# UART_2_MUX.net
KiCad netlist of a schematic drawn in Altium Designer
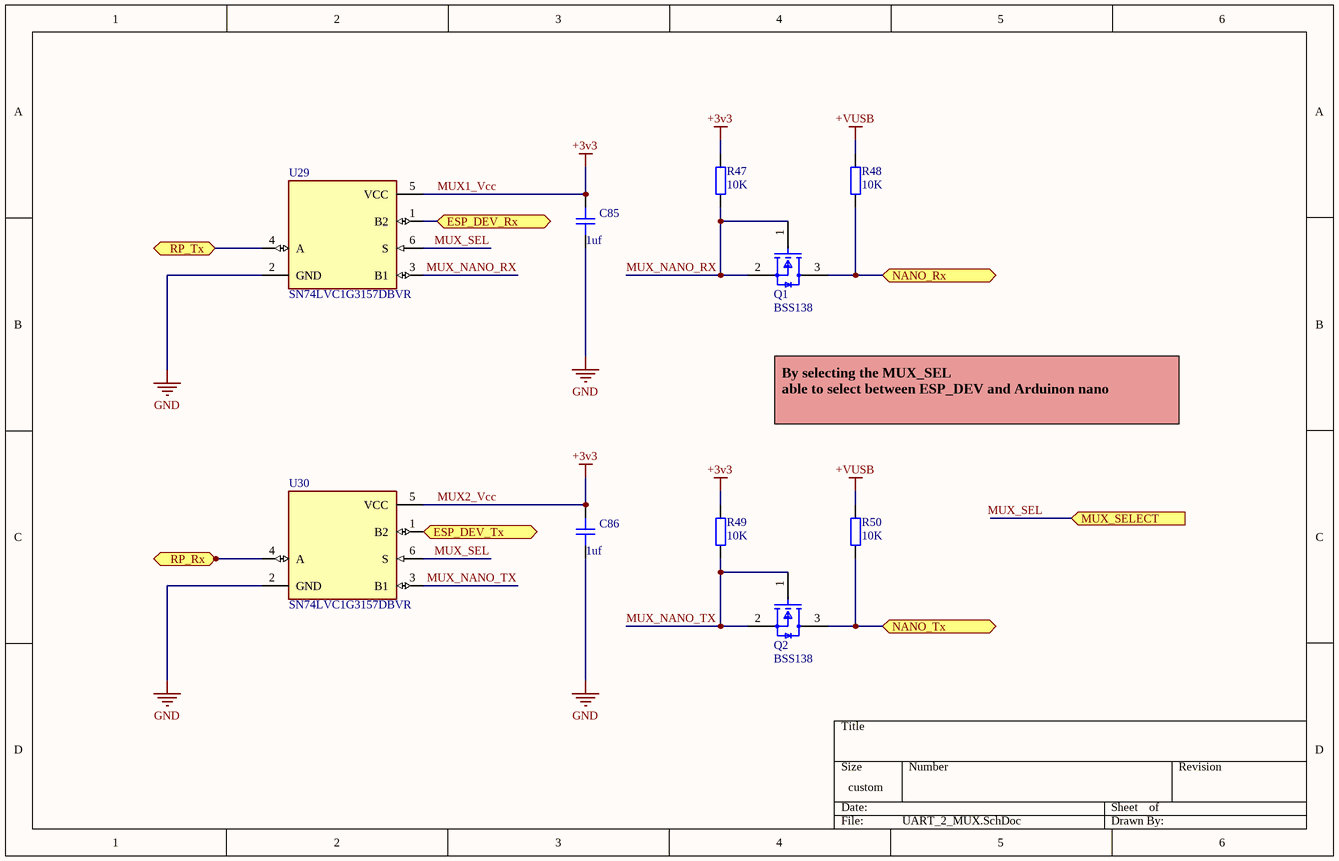
[diagram p0: UART_2_MUX.SchDoc]

(export (version "E")
  (design (tool "Eeschema 10.0.6"))
  (components
    (comp (ref "C85")
      (value "1uf")
      (footprint "CAP_0603")
      (description "Capacitor SMD 0603")
      (libsource (lib "Schematic-Lib-PhilsLab") (part "CAP_0603"))
    )
    (comp (ref "C86")
      (value "1uf")
      (footprint "CAP_0603")
      (description "Capacitor SMD 0603")
      (libsource (lib "Schematic-Lib-PhilsLab") (part "CAP_0603"))
    )
    (comp (ref "Q1")
      (value "BSS138")
      (footprint "FP-318-08-IPC_B")
      (description "MOSFET N-CH 50V 220MA SOT-23")
      (libsource (lib "Altium Content Vault") (part "3b9c635fedb024a5347a57b145af9cc"))
    )
    (comp (ref "Q2")
      (value "BSS138")
      (footprint "FP-318-08-IPC_B")
      (description "MOSFET N-CH 50V 220MA SOT-23")
      (libsource (lib "Altium Content Vault") (part "3b9c635fedb024a5347a57b145af9cc"))
    )
    (comp (ref "R47")
      (value "10K")
      (footprint "RES_0603")
      (description "Resistor SMD 0603")
      (libsource (lib "Schematic-Lib-PhilsLab") (part "RES_0603"))
    )
    (comp (ref "R48")
      (value "10K")
      (footprint "RES_0603")
      (description "Resistor SMD 0603")
      (libsource (lib "Schematic-Lib-PhilsLab") (part "RES_0603"))
    )
    (comp (ref "R49")
      (value "10K")
      (footprint "RES_0603")
      (description "Resistor SMD 0603")
      (libsource (lib "Schematic-Lib-PhilsLab") (part "RES_0603"))
    )
    (comp (ref "R50")
      (value "10K")
      (footprint "RES_0603")
      (description "Resistor SMD 0603")
      (libsource (lib "Schematic-Lib-PhilsLab") (part "RES_0603"))
    )
    (comp (ref "U29")
      (value "SN74LVC1G3157DBVR")
      (footprint "FP-DBV0006A-IPC_C")
      (description "IC SWITCH SPDT SOT23-6")
      (libsource (lib "Altium Content Vault") (part "14cfcf06f1431fbc89496e2a44d6624"))
    )
    (comp (ref "U30")
      (value "SN74LVC1G3157DBVR")
      (footprint "FP-DBV0006A-IPC_C")
      (description "IC SWITCH SPDT SOT23-6")
      (libsource (lib "Altium Content Vault") (part "14cfcf06f1431fbc89496e2a44d6624"))
    )
  )
  (nets
    (net (code "1") (name "+3v3") (class "Default")
      (node (ref "C85") (pin "2") (pinfunction "2_2") (pintype "passive"))
      (node (ref "C86") (pin "2") (pinfunction "2_2") (pintype "passive"))
      (node (ref "R47") (pin "1") (pinfunction "1_1") (pintype "passive"))
      (node (ref "R49") (pin "1") (pinfunction "1_1") (pintype "passive"))
      (node (ref "U29") (pin "5") (pinfunction "VCC_5") (pintype "power_in"))
      (node (ref "U30") (pin "5") (pinfunction "VCC_5") (pintype "power_in"))
    )
    (net (code "2") (name "+VUSB") (class "Default")
      (node (ref "R48") (pin "1") (pinfunction "1_1") (pintype "passive"))
      (node (ref "R50") (pin "1") (pinfunction "1_1") (pintype "passive"))
    )
    (net (code "3") (name "/ESP_DEV_Rx") (class "Default")
      (node (ref "U29") (pin "1") (pinfunction "B2_1") (pintype "bidirectional"))
    )
    (net (code "4") (name "/ESP_DEV_Tx") (class "Default")
      (node (ref "U30") (pin "1") (pinfunction "B2_1") (pintype "bidirectional"))
    )
    (net (code "5") (name "/MUX_NANO_RX") (class "Default")
      (node (ref "Q1") (pin "1") (pinfunction "G_1") (pintype "passive"))
      (node (ref "Q1") (pin "2") (pinfunction "S_2") (pintype "passive"))
      (node (ref "R47") (pin "2") (pinfunction "2_2") (pintype "passive"))
      (node (ref "U29") (pin "3") (pinfunction "B1_3") (pintype "bidirectional"))
    )
    (net (code "6") (name "/MUX_NANO_TX") (class "Default")
      (node (ref "Q2") (pin "1") (pinfunction "G_1") (pintype "passive"))
      (node (ref "Q2") (pin "2") (pinfunction "S_2") (pintype "passive"))
      (node (ref "R49") (pin "2") (pinfunction "2_2") (pintype "passive"))
      (node (ref "U30") (pin "3") (pinfunction "B1_3") (pintype "bidirectional"))
    )
    (net (code "7") (name "/MUX_SEL") (class "Default")
      (node (ref "U29") (pin "6") (pinfunction "S_6") (pintype "input"))
      (node (ref "U30") (pin "6") (pinfunction "S_6") (pintype "input"))
    )
    (net (code "8") (name "/NANO_Rx") (class "Default")
      (node (ref "Q1") (pin "3") (pinfunction "D_3") (pintype "passive"))
      (node (ref "R48") (pin "2") (pinfunction "2_2") (pintype "passive"))
    )
    (net (code "9") (name "/NANO_Tx") (class "Default")
      (node (ref "Q2") (pin "3") (pinfunction "D_3") (pintype "passive"))
      (node (ref "R50") (pin "2") (pinfunction "2_2") (pintype "passive"))
    )
    (net (code "10") (name "/RP_Rx") (class "Default")
      (node (ref "U30") (pin "4") (pinfunction "A_4") (pintype "bidirectional"))
    )
    (net (code "11") (name "/RP_Tx") (class "Default")
      (node (ref "U29") (pin "4") (pinfunction "A_4") (pintype "bidirectional"))
    )
    (net (code "12") (name "GND") (class "Default")
      (node (ref "C85") (pin "1") (pinfunction "1_1") (pintype "passive"))
      (node (ref "C86") (pin "1") (pinfunction "1_1") (pintype "passive"))
      (node (ref "U29") (pin "2") (pinfunction "GND_2") (pintype "power_in"))
      (node (ref "U30") (pin "2") (pinfunction "GND_2") (pintype "power_in"))
    )
  )
)
